# as5600_adapter.net
KiCad netlist of a schematic drawn in EAGLE
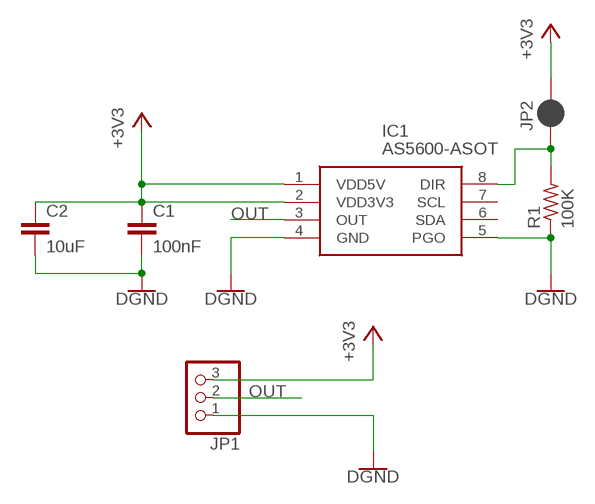
[diagram p0: schematic, sheet 1]

(export (version "E")
  (design (tool "Eeschema 10.0.6"))
  (components
    (comp (ref "C1")
      (value "100nF")
      (footprint "eagle-import:C0603")
      (libsource (lib "eagle-import") (part "C-EUC0603"))
    )
    (comp (ref "C2")
      (value "10uF")
      (footprint "eagle-import:C0805")
      (libsource (lib "eagle-import") (part "C-EUC0805"))
    )
    (comp (ref "IC1")
      (value "AS5600-ASOT")
      (footprint "eagle-import:SOIC127P600X175-8N")
      (fields (field (name "MOUSER_PART_NUMBER") "985-AS5600-ASOT"))
      (libsource (lib "eagle-import") (part "AS5600-ASOT"))
    )
    (comp (ref "JP1")
      (value "PINHD-1X3")
      (footprint "eagle-import:1X03")
      (libsource (lib "eagle-import") (part "PINHD-1X3"))
    )
    (comp (ref "JP2")
      (value "JUMPER-SMT_2_NC_PASTE_NO-SILK")
      (footprint "eagle-import:SMT-JUMPER_2_NC_PASTE_NO-SILK")
      (libsource (lib "eagle-import") (part "JUMPER-SMT_2_NC_PASTE_NO-SILK"))
    )
    (comp (ref "R1")
      (value "100K")
      (footprint "eagle-import:R0603")
      (libsource (lib "eagle-import") (part "R-US_R0603"))
    )
  )
  (nets
    (net (code "1") (name "+3V3") (class "Default")
      (node (ref "C1") (pin "1") (pinfunction "1_1") (pintype "passive"))
      (node (ref "C2") (pin "1") (pinfunction "1_1") (pintype "passive"))
      (node (ref "IC1") (pin "1") (pinfunction "VDD5V_1") (pintype "bidirectional"))
      (node (ref "IC1") (pin "2") (pinfunction "VDD3V3_2") (pintype "bidirectional"))
      (node (ref "JP1") (pin "3") (pinfunction "3_3") (pintype "passive"))
      (node (ref "JP2") (pin "2") (pinfunction "2_2") (pintype "passive"))
    )
    (net (code "2") (name "/OUT") (class "Default")
      (node (ref "IC1") (pin "3") (pinfunction "OUT_3") (pintype "bidirectional"))
      (node (ref "JP1") (pin "2") (pinfunction "2_2") (pintype "passive"))
    )
    (net (code "3") (name "DGND") (class "Default")
      (node (ref "C1") (pin "2") (pinfunction "2_2") (pintype "passive"))
      (node (ref "C2") (pin "2") (pinfunction "2_2") (pintype "passive"))
      (node (ref "IC1") (pin "4") (pinfunction "GND_4") (pintype "bidirectional"))
      (node (ref "IC1") (pin "5") (pinfunction "PGO_5") (pintype "bidirectional"))
      (node (ref "JP1") (pin "1") (pinfunction "1_1") (pintype "passive"))
      (node (ref "R1") (pin "1") (pinfunction "1_1") (pintype "passive"))
    )
    (net (code "4") (name "Net-(IC1-DIR)") (class "Default")
      (node (ref "IC1") (pin "8") (pinfunction "DIR_8") (pintype "bidirectional"))
      (node (ref "JP2") (pin "1") (pinfunction "1_1") (pintype "passive"))
      (node (ref "R1") (pin "2") (pinfunction "2_2") (pintype "passive"))
    )
    (net (code "5") (name "unconnected-(IC1-SCL-Pad7)") (class "Default")
      (node (ref "IC1") (pin "7") (pinfunction "SCL_7") (pintype "bidirectional"))
    )
    (net (code "6") (name "unconnected-(IC1-SDA-Pad6)") (class "Default")
      (node (ref "IC1") (pin "6") (pinfunction "SDA_6") (pintype "bidirectional"))
    )
  )
)
